# photoresistor.net
KiCad netlist of a schematic drawn in EAGLE
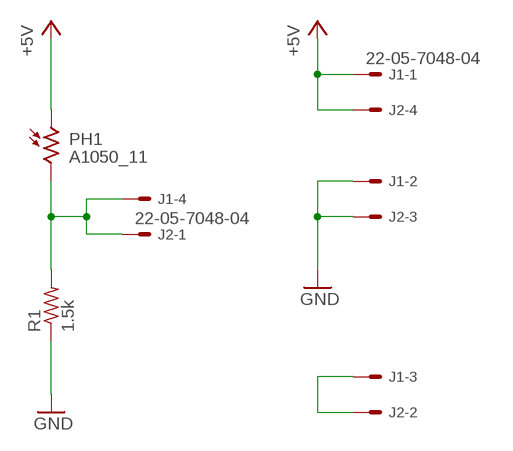
[diagram p0: schematic, sheet 1]

(export (version "E")
  (design (tool "Eeschema 10.0.6"))
  (components
    (comp (ref "J1")
      (value "22-05-7048-04")
      (footprint "eagle-import:7395-04")
      (libsource (lib "eagle-import") (part "22-?-0405-7048"))
    )
    (comp (ref "J2")
      (value "22-05-7048-04")
      (footprint "eagle-import:7395-04")
      (libsource (lib "eagle-import") (part "22-?-0405-7048"))
    )
    (comp (ref "PH1")
      (value "A1050_11")
      (footprint "eagle-import:T0-46-A10XX")
      (libsource (lib "eagle-import") (part "A1050_11"))
    )
    (comp (ref "R1")
      (value "1.5k")
      (footprint "eagle-import:M0805")
      (libsource (lib "eagle-import") (part "R-US_M0805"))
    )
  )
  (nets
    (net (code "1") (name "+5V") (class "Default")
      (node (ref "J1") (pin "1") (pinfunction "S_1") (pintype "passive"))
      (node (ref "J2") (pin "4") (pinfunction "S_4") (pintype "passive"))
      (node (ref "PH1") (pin "1") (pinfunction "1_1") (pintype "passive"))
    )
    (net (code "2") (name "GND") (class "Default")
      (node (ref "J1") (pin "2") (pinfunction "S_2") (pintype "passive"))
      (node (ref "J2") (pin "3") (pinfunction "S_3") (pintype "passive"))
      (node (ref "R1") (pin "1") (pinfunction "1_1") (pintype "passive"))
    )
    (net (code "3") (name "Net-(J1C-S)") (class "Default")
      (node (ref "J1") (pin "3") (pinfunction "S_3") (pintype "passive"))
      (node (ref "J2") (pin "2") (pinfunction "S_2") (pintype "passive"))
    )
    (net (code "4") (name "Net-(J1D-S)") (class "Default")
      (node (ref "J1") (pin "4") (pinfunction "S_4") (pintype "passive"))
      (node (ref "J2") (pin "1") (pinfunction "S_1") (pintype "passive"))
      (node (ref "PH1") (pin "2") (pinfunction "2_2") (pintype "passive"))
      (node (ref "R1") (pin "2") (pinfunction "2_2") (pintype "passive"))
    )
  )
)
